# filtro_salida_gpio3.net
KiCad netlist of a schematic drawn in Altium Designer
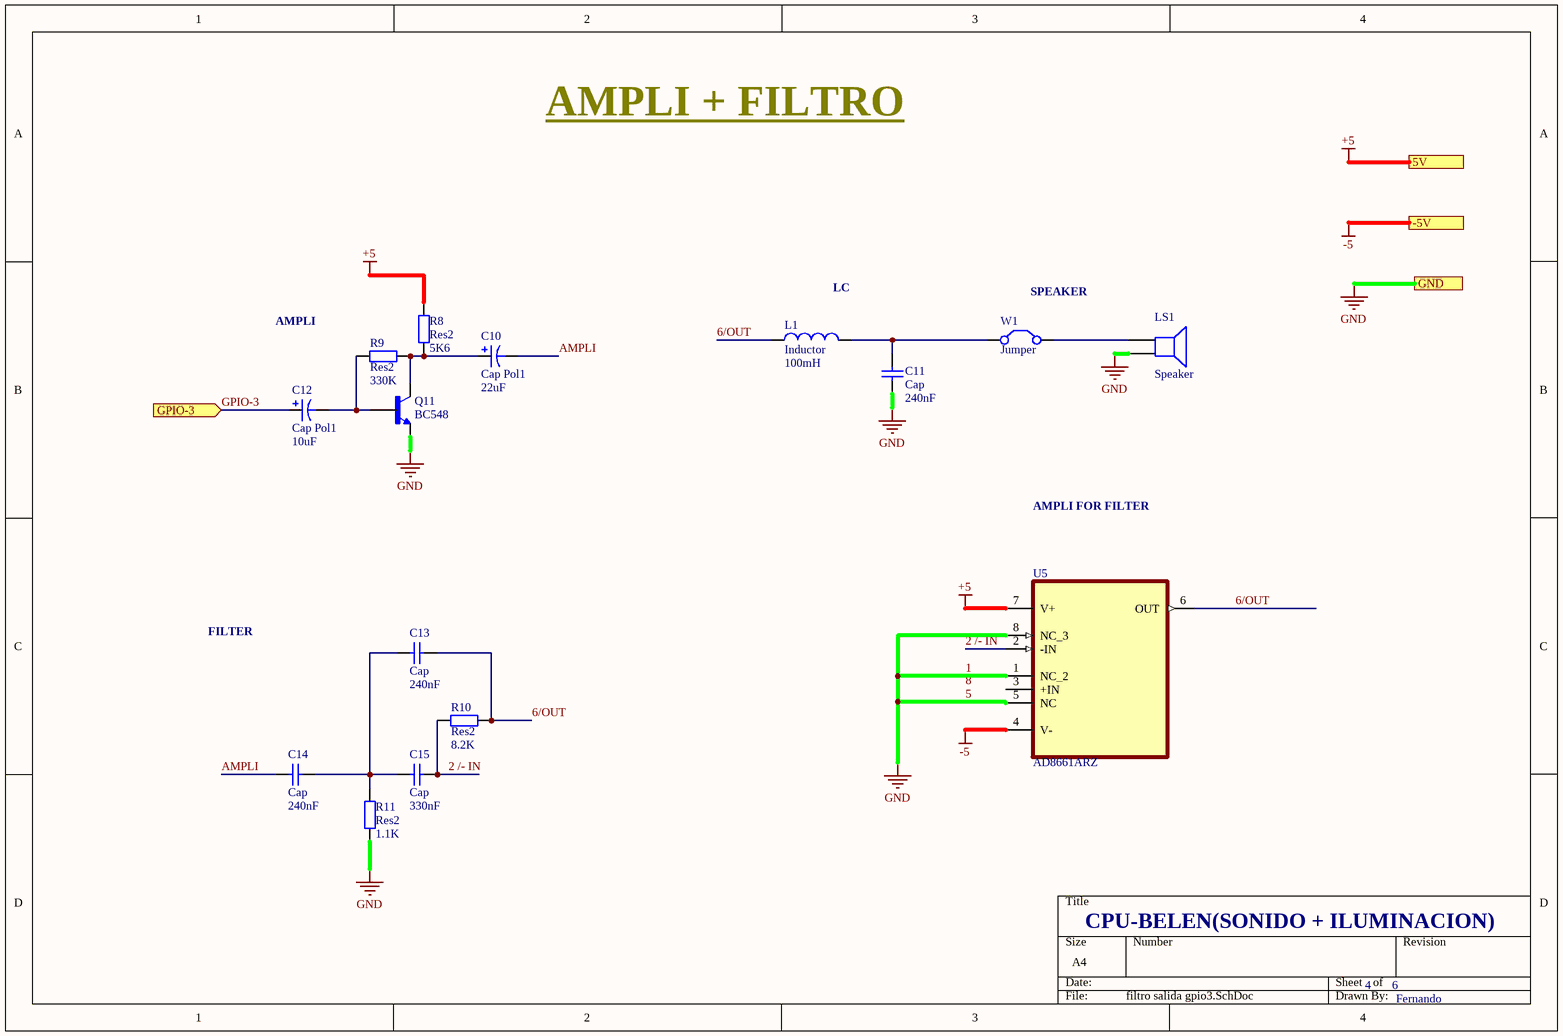
[diagram p0: filtro salida gpio3.SchDoc]

(export (version "E")
  (design (tool "Eeschema 10.0.6"))
  (components
    (comp (ref "C10")
      (value "Cap Pol1")
      (footprint "RB7.6-15")
      (description "Polarized Capacitor (Radial)")
      (fields (field (name "ALTIUM_VALUE") "22uF") (field (name "PUBLISHER") "Altium Limited"))
      (libsource (lib "Miscellaneous Devices") (part "Cap Pol1"))
    )
    (comp (ref "C11")
      (value "Cap")
      (footprint "RAD-0.3")
      (description "Capacitor")
      (fields (field (name "ALTIUM_VALUE") "240nF") (field (name "PUBLISHER") "Altium Limited"))
      (libsource (lib "Miscellaneous Devices") (part "Cap"))
    )
    (comp (ref "C12")
      (value "Cap Pol1")
      (footprint "RB7.6-15")
      (description "Polarized Capacitor (Radial)")
      (fields (field (name "ALTIUM_VALUE") "10uF") (field (name "PUBLISHER") "Altium Limited"))
      (libsource (lib "Miscellaneous Devices") (part "Cap Pol1"))
    )
    (comp (ref "C13")
      (value "Cap")
      (footprint "RAD-0.3")
      (description "Capacitor")
      (fields (field (name "ALTIUM_VALUE") "240nF") (field (name "PUBLISHER") "Altium Limited"))
      (libsource (lib "Miscellaneous Devices") (part "Cap"))
    )
    (comp (ref "C14")
      (value "Cap")
      (footprint "RAD-0.3")
      (description "Capacitor")
      (fields (field (name "ALTIUM_VALUE") "240nF") (field (name "PUBLISHER") "Altium Limited"))
      (libsource (lib "Miscellaneous Devices") (part "Cap"))
    )
    (comp (ref "C15")
      (value "Cap")
      (footprint "RAD-0.3")
      (description "Capacitor")
      (fields (field (name "ALTIUM_VALUE") "330nF") (field (name "PUBLISHER") "Altium Limited"))
      (libsource (lib "Miscellaneous Devices") (part "Cap"))
    )
    (comp (ref "L1")
      (value "Inductor")
      (footprint "AXIAL-0.4")
      (fields (field (name "ALTIUM_VALUE") "100mH") (field (name "PUBLISHER") "Altium Limited"))
      (libsource (lib "Miscellaneous Devices") (part "Inductor"))
    )
    (comp (ref "LS1")
      (value "Speaker")
      (footprint "PIN2")
      (description "Loudspeaker")
      (fields (field (name "PUBLISHER") "Altium Limited"))
      (libsource (lib "Miscellaneous Devices") (part "Speaker"))
    )
    (comp (ref "Q11")
      (value "BC548")
      (footprint "TO92127P520H533-3")
      (description "Bipolar (BJT) Transistor NPN 30V 100mA 300MHz 500mW Through Hole TO-92-3")
      (fields (field (name "MF") "ON Semiconductor"))
      (libsource (lib "BC548") (part "BC548"))
    )
    (comp (ref "R8")
      (value "Res2")
      (footprint "AXIAL-0.4")
      (description "Resistor")
      (fields (field (name "ALTIUM_VALUE") "5K6") (field (name "PUBLISHER") "Altium Limited"))
      (libsource (lib "Miscellaneous Devices") (part "Res2"))
    )
    (comp (ref "R9")
      (value "Res2")
      (footprint "AXIAL-0.4")
      (description "Resistor")
      (fields (field (name "ALTIUM_VALUE") "330K") (field (name "PUBLISHER") "Altium Limited"))
      (libsource (lib "") (part "Res2_1"))
    )
    (comp (ref "R10")
      (value "Res2")
      (footprint "AXIAL-0.4")
      (description "Resistor")
      (fields (field (name "ALTIUM_VALUE") "8.2K") (field (name "PUBLISHER") "Altium Limited"))
      (libsource (lib "") (part "Res2_1"))
    )
    (comp (ref "R11")
      (value "Res2")
      (footprint "AXIAL-0.4")
      (description "Resistor")
      (fields (field (name "ALTIUM_VALUE") "1.1K") (field (name "PUBLISHER") "Altium Limited"))
      (libsource (lib "Miscellaneous Devices") (part "Res2"))
    )
    (comp (ref "U5")
      (value "AD8661ARZ")
      (footprint "SOIC127P600X175-8N")
      (description "General Purpose Amplifier 1 Circuit Rail-to-Rail 8-SOIC")
      (fields (field (name "MF") "Analog Devices"))
      (libsource (lib "AD8661ARZ") (part "AD8661ARZ"))
    )
    (comp (ref "W1")
      (value "Jumper")
      (footprint "RAD-0.2")
      (description "Jumper Wire")
      (fields (field (name "PUBLISHER") "Altium Limited"))
      (libsource (lib "Miscellaneous Devices") (part "Jumper"))
    )
  )
  (nets
    (net (code "1") (name "+5") (class "Default")
      (node (ref "R8") (pin "2") (pinfunction "2_2") (pintype "passive"))
      (node (ref "U5") (pin "7") (pinfunction "V+_7") (pintype "power_in"))
    )
    (net (code "2") (name "-5") (class "Default")
      (node (ref "U5") (pin "4") (pinfunction "V-_4") (pintype "power_in"))
    )
    (net (code "3") (name "/2 {slash}- IN") (class "Default")
      (node (ref "C15") (pin "2") (pinfunction "2_2") (pintype "passive"))
      (node (ref "R10") (pin "1") (pinfunction "1_1") (pintype "passive"))
      (node (ref "U5") (pin "2") (pinfunction "-IN_2") (pintype "input"))
    )
    (net (code "4") (name "/6{slash}OUT") (class "Default")
      (node (ref "C13") (pin "2") (pinfunction "2_2") (pintype "passive"))
      (node (ref "L1") (pin "1") (pinfunction "1_1") (pintype "passive"))
      (node (ref "R10") (pin "2") (pinfunction "2_2") (pintype "passive"))
      (node (ref "U5") (pin "6") (pinfunction "OUT_6") (pintype "output"))
    )
    (net (code "6") (name "/AMPLI") (class "Default")
      (node (ref "C10") (pin "2") (pinfunction "2_2") (pintype "passive"))
      (node (ref "C14") (pin "1") (pinfunction "1_1") (pintype "passive"))
    )
    (net (code "7") (name "/GPIO-3") (class "Default")
      (node (ref "C12") (pin "1") (pinfunction "1_1") (pintype "passive"))
    )
    (net (code "8") (name "GND") (class "Default")
      (node (ref "C11") (pin "1") (pinfunction "1_1") (pintype "passive"))
      (node (ref "LS1") (pin "2") (pinfunction "2_2") (pintype "passive"))
      (node (ref "Q11") (pin "3") (pinfunction "E_3") (pintype "passive"))
      (node (ref "R11") (pin "1") (pinfunction "1_1") (pintype "passive"))
      (node (ref "U5") (pin "1") (pinfunction "NC_2_1") (pintype "passive"))
      (node (ref "U5") (pin "5") (pinfunction "NC_5") (pintype "passive"))
      (node (ref "U5") (pin "8") (pinfunction "NC_3_8") (pintype "input"))
    )
    (net (code "9") (name "Net-(C13-Pad1)") (class "Default")
      (node (ref "C13") (pin "1") (pinfunction "1_1") (pintype "passive"))
      (node (ref "C14") (pin "2") (pinfunction "2_2") (pintype "passive"))
      (node (ref "C15") (pin "1") (pinfunction "1_1") (pintype "passive"))
      (node (ref "R11") (pin "2") (pinfunction "2_2") (pintype "passive"))
    )
    (net (code "10") (name "Net-(Q11-B)") (class "Default")
      (node (ref "C12") (pin "2") (pinfunction "2_2") (pintype "passive"))
      (node (ref "Q11") (pin "2") (pinfunction "B_2") (pintype "passive"))
      (node (ref "R9") (pin "1") (pinfunction "1_1") (pintype "passive"))
    )
    (net (code "11") (name "Net-(Q11-C)") (class "Default")
      (node (ref "C10") (pin "1") (pinfunction "1_1") (pintype "passive"))
      (node (ref "Q11") (pin "1") (pinfunction "C_1") (pintype "passive"))
      (node (ref "R8") (pin "1") (pinfunction "1_1") (pintype "passive"))
      (node (ref "R9") (pin "2") (pinfunction "2_2") (pintype "passive"))
    )
    (net (code "12") (name "Net-(W1-C1)") (class "Default")
      (node (ref "C11") (pin "2") (pinfunction "2_2") (pintype "passive"))
      (node (ref "L1") (pin "2") (pinfunction "2_2") (pintype "passive"))
      (node (ref "W1") (pin "1") (pinfunction "C1_1") (pintype "passive"))
    )
    (net (code "13") (name "Net-(W1-C2)") (class "Default")
      (node (ref "LS1") (pin "1") (pinfunction "1_1") (pintype "passive"))
      (node (ref "W1") (pin "2") (pinfunction "C2_2") (pintype "passive"))
    )
    (net (code "14") (name "unconnected-(U5-+IN-Pad3)") (class "Default")
      (node (ref "U5") (pin "3") (pinfunction "+IN_3") (pintype "passive"))
    )
  )
)
